# Project.net
KiCad netlist of a schematic drawn in Altium Designer
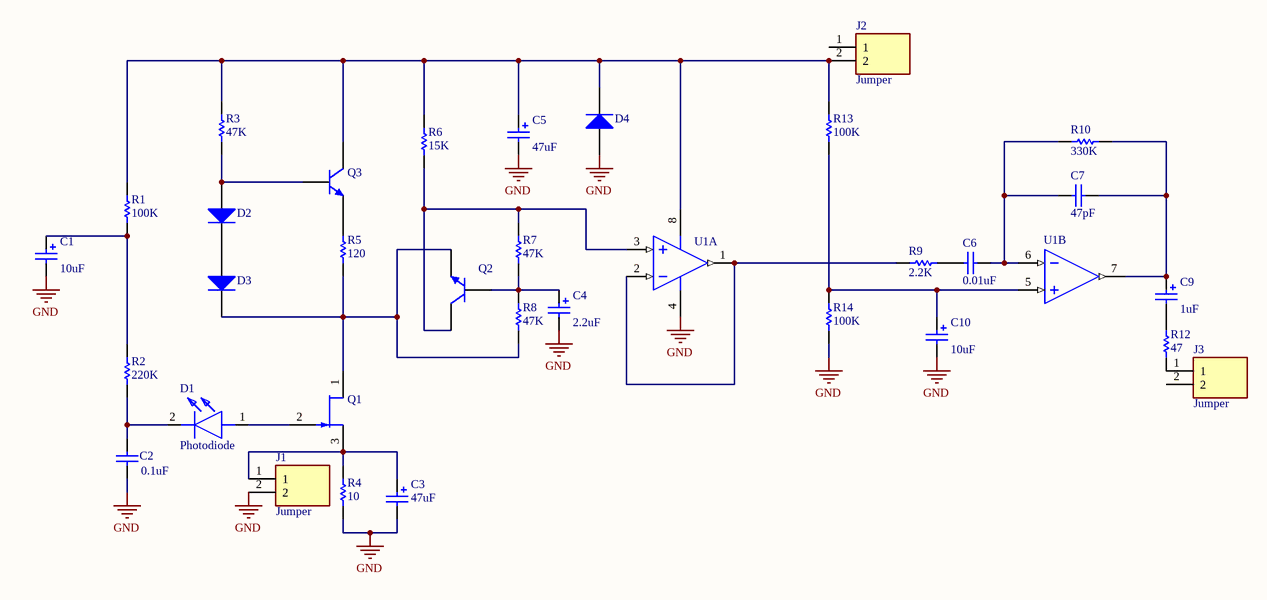
[diagram p0: Project.SchDoc]

(export (version "E")
  (design (tool "Eeschema 10.0.6"))
  (components
    (comp (ref "C1")
      (value "10uF")
      (footprint "Capacitor - Pol")
      (description "Polarized Capacitor (Radial)")
      (fields (field (name "Comment") "Cap Pol1") (field (name "PUBLISHER") "Altium Limited"))
      (libsource (lib "Standar_Components") (part "Cap Pol1"))
    )
    (comp (ref "C2")
      (value "0.1uF")
      (footprint "Capacitor")
      (description "Capacitor")
      (fields (field (name "Comment") "Cap") (field (name "PUBLISHER") "Altium Limited"))
      (libsource (lib "Standar_Components") (part "Cap"))
    )
    (comp (ref "C3")
      (value "47uF")
      (footprint "Capacitor - Pol")
      (description "Polarized Capacitor (Radial)")
      (fields (field (name "Comment") "Cap Pol1") (field (name "PUBLISHER") "Altium Limited"))
      (libsource (lib "Standar_Components") (part "Cap Pol1"))
    )
    (comp (ref "C4")
      (value "2.2uF")
      (footprint "Capacitor - Pol")
      (description "Polarized Capacitor (Radial)")
      (fields (field (name "Comment") "Cap Pol1") (field (name "PUBLISHER") "Altium Limited"))
      (libsource (lib "Standar_Components") (part "Cap Pol1"))
    )
    (comp (ref "C5")
      (value "47uF")
      (footprint "Capacitor - Pol")
      (description "Polarized Capacitor (Radial)")
      (fields (field (name "Comment") "Cap Pol1") (field (name "PUBLISHER") "Altium Limited"))
      (libsource (lib "Standar_Components") (part "Cap Pol1"))
    )
    (comp (ref "C6")
      (value "0.01uF")
      (footprint "Capacitor")
      (description "Capacitor")
      (fields (field (name "Comment") "Cap") (field (name "PUBLISHER") "Altium Limited"))
      (libsource (lib "Standar_Components") (part "Cap"))
    )
    (comp (ref "C7")
      (value "47pF")
      (footprint "Capacitor")
      (description "Capacitor")
      (fields (field (name "Comment") "Cap") (field (name "PUBLISHER") "Altium Limited"))
      (libsource (lib "Standar_Components") (part "Cap"))
    )
    (comp (ref "C9")
      (value "1uF")
      (footprint "Capacitor - Pol")
      (description "Polarized Capacitor (Radial)")
      (fields (field (name "Comment") "Cap Pol1") (field (name "PUBLISHER") "Altium Limited"))
      (libsource (lib "Standar_Components") (part "Cap Pol1"))
    )
    (comp (ref "C10")
      (value "10uF")
      (footprint "Capacitor - Pol")
      (description "Polarized Capacitor (Radial)")
      (fields (field (name "Comment") "Cap Pol1") (field (name "PUBLISHER") "Altium Limited"))
      (libsource (lib "Standar_Components") (part "Cap Pol1"))
    )
    (comp (ref "D1")
      (value "Photodiode")
      (footprint "Diode")
      (libsource (lib "Standar_Components") (part "Photodiode"))
    )
    (comp (ref "D2")
      (value "Diode 1N5408")
      (footprint "Diode")
      (description "3 Amp Medium Power Silicon Rectifier Diode")
      (fields (field (name "PUBLISHER") "Altium Limited"))
      (libsource (lib "Standar_Components") (part "Diode 1N5408"))
    )
    (comp (ref "D3")
      (value "Diode 1N5408")
      (footprint "Diode")
      (description "3 Amp Medium Power Silicon Rectifier Diode")
      (fields (field (name "PUBLISHER") "Altium Limited"))
      (libsource (lib "Standar_Components") (part "Diode 1N5408"))
    )
    (comp (ref "D4")
      (value "Diode 1N5408")
      (footprint "Diode")
      (description "3 Amp Medium Power Silicon Rectifier Diode")
      (fields (field (name "PUBLISHER") "Altium Limited"))
      (libsource (lib "Standar_Components") (part "Diode 1N5408"))
    )
    (comp (ref "J1")
      (value "Jumper")
      (footprint "JUMPER")
      (libsource (lib "Standar_Components") (part "Jumper"))
    )
    (comp (ref "J2")
      (value "Jumper")
      (footprint "JUMPER")
      (libsource (lib "Standar_Components") (part "Jumper"))
    )
    (comp (ref "J3")
      (value "Jumper")
      (footprint "JUMPER")
      (libsource (lib "Standar_Components") (part "Jumper"))
    )
    (comp (ref "Q1")
      (value "JFET-N")
      (footprint "TRANSISTOR")
      (description "N-Channel JFET")
      (fields (field (name "PUBLISHER") "Altium Limited"))
      (libsource (lib "Standar_Components") (part "JFET-N"))
    )
    (comp (ref "Q2")
      (value "NPN")
      (footprint "TRANSISTOR")
      (description "NPN Bipolar Transistor")
      (fields (field (name "PUBLISHER") "Altium Limited"))
      (libsource (lib "Standar_Components") (part "NPN"))
    )
    (comp (ref "Q3")
      (value "NPN")
      (footprint "TRANSISTOR")
      (description "NPN Bipolar Transistor")
      (fields (field (name "PUBLISHER") "Altium Limited"))
      (libsource (lib "Standar_Components") (part "NPN"))
    )
    (comp (ref "R1")
      (value "100K")
      (footprint "RES - Axial 0.6")
      (description "Resistor")
      (fields (field (name "Comment") "Res1") (field (name "PUBLISHER") "Altium Limited"))
      (libsource (lib "Standar_Components") (part "Res1"))
    )
    (comp (ref "R2")
      (value "220K")
      (footprint "RES - Axial 0.6")
      (description "Resistor")
      (fields (field (name "Comment") "Res1") (field (name "PUBLISHER") "Altium Limited"))
      (libsource (lib "Standar_Components") (part "Res1"))
    )
    (comp (ref "R3")
      (value "47K")
      (footprint "RES - Axial 0.6")
      (description "Resistor")
      (fields (field (name "Comment") "Res1") (field (name "PUBLISHER") "Altium Limited"))
      (libsource (lib "Standar_Components") (part "Res1"))
    )
    (comp (ref "R4")
      (value "10")
      (footprint "RES - Axial 0.6")
      (description "Resistor")
      (fields (field (name "Comment") "Res1") (field (name "PUBLISHER") "Altium Limited"))
      (libsource (lib "Standar_Components") (part "Res1"))
    )
    (comp (ref "R5")
      (value "120")
      (footprint "RES - Axial 0.6")
      (description "Resistor")
      (fields (field (name "Comment") "Res1") (field (name "PUBLISHER") "Altium Limited"))
      (libsource (lib "Standar_Components") (part "Res1"))
    )
    (comp (ref "R6")
      (value "15K")
      (footprint "RES - Axial 0.6")
      (description "Resistor")
      (fields (field (name "Comment") "Res1") (field (name "PUBLISHER") "Altium Limited"))
      (libsource (lib "Standar_Components") (part "Res1"))
    )
    (comp (ref "R7")
      (value "47K")
      (footprint "RES - Axial 0.6")
      (description "Resistor")
      (fields (field (name "Comment") "Res1") (field (name "PUBLISHER") "Altium Limited"))
      (libsource (lib "Standar_Components") (part "Res1"))
    )
    (comp (ref "R8")
      (value "47K")
      (footprint "RES - Axial 0.6")
      (description "Resistor")
      (fields (field (name "Comment") "Res1") (field (name "PUBLISHER") "Altium Limited"))
      (libsource (lib "Standar_Components") (part "Res1"))
    )
    (comp (ref "R9")
      (value "2.2K")
      (footprint "RES - Axial 0.6")
      (description "Resistor")
      (fields (field (name "Comment") "Res1") (field (name "PUBLISHER") "Altium Limited"))
      (libsource (lib "Standar_Components") (part "Res1"))
    )
    (comp (ref "R10")
      (value "330K")
      (footprint "RES - Axial 0.6")
      (description "Resistor")
      (fields (field (name "Comment") "Res1") (field (name "PUBLISHER") "Altium Limited"))
      (libsource (lib "Standar_Components") (part "Res1"))
    )
    (comp (ref "R12")
      (value "47")
      (footprint "RES - Axial 0.6")
      (description "Resistor")
      (fields (field (name "Comment") "Res1") (field (name "PUBLISHER") "Altium Limited"))
      (libsource (lib "Standar_Components") (part "Res1"))
    )
    (comp (ref "R13")
      (value "100K")
      (footprint "RES - Axial 0.6")
      (description "Resistor")
      (fields (field (name "Comment") "Res1") (field (name "PUBLISHER") "Altium Limited"))
      (libsource (lib "Standar_Components") (part "Res1"))
    )
    (comp (ref "R14")
      (value "100K")
      (footprint "RES - Axial 0.6")
      (description "Resistor")
      (fields (field (name "Comment") "Res1") (field (name "PUBLISHER") "Altium Limited"))
      (libsource (lib "Standar_Components") (part "Res1"))
    )
    (comp (ref "U1")
      (value "LM833N/NOPB")
      (footprint "DIP8")
      (description "AUDIO AMPLIFIER")
      (fields (field (name "MANUFACTURER") "TI National Semiconductor"))
      (libsource (lib "Components") (part "LM833N/NOPB"))
    )
  )
  (nets
    (net (code "1") (name "GND") (class "Default")
      (node (ref "C1") (pin "2") (pinfunction "2_2") (pintype "passive"))
      (node (ref "C10") (pin "2") (pinfunction "2_2") (pintype "passive"))
      (node (ref "C2") (pin "1") (pinfunction "1_1") (pintype "passive"))
      (node (ref "C3") (pin "2") (pinfunction "2_2") (pintype "passive"))
      (node (ref "C4") (pin "2") (pinfunction "2_2") (pintype "passive"))
      (node (ref "C5") (pin "2") (pinfunction "2_2") (pintype "passive"))
      (node (ref "D4") (pin "1") (pinfunction "A_1") (pintype "passive"))
      (node (ref "J1") (pin "2") (pinfunction "2_2") (pintype "passive"))
      (node (ref "R14") (pin "1") (pinfunction "1_1") (pintype "passive"))
      (node (ref "R4") (pin "1") (pinfunction "1_1") (pintype "passive"))
      (node (ref "U1") (pin "4") (pinfunction "V-_4") (pintype "power_in"))
    )
    (net (code "2") (name "Net-(C1-Pad1)") (class "Default")
      (node (ref "C1") (pin "1") (pinfunction "1_1") (pintype "passive"))
      (node (ref "R1") (pin "1") (pinfunction "1_1") (pintype "passive"))
      (node (ref "R2") (pin "2") (pinfunction "2_2") (pintype "passive"))
    )
    (net (code "3") (name "Net-(C6-Pad2)") (class "Default")
      (node (ref "C6") (pin "2") (pinfunction "2_2") (pintype "passive"))
      (node (ref "R9") (pin "1") (pinfunction "1_1") (pintype "passive"))
    )
    (net (code "4") (name "Net-(C9-Pad2)") (class "Default")
      (node (ref "C9") (pin "2") (pinfunction "2_2") (pintype "passive"))
      (node (ref "R12") (pin "2") (pinfunction "2_2") (pintype "passive"))
    )
    (net (code "5") (name "Net-(D1-A)") (class "Default")
      (node (ref "D1") (pin "1") (pinfunction "A_1") (pintype "passive"))
      (node (ref "Q1") (pin "2") (pinfunction "G_2") (pintype "passive"))
    )
    (net (code "6") (name "Net-(D1-K)") (class "Default")
      (node (ref "C2") (pin "2") (pinfunction "2_2") (pintype "passive"))
      (node (ref "D1") (pin "2") (pinfunction "K_2") (pintype "passive"))
      (node (ref "R2") (pin "1") (pinfunction "1_1") (pintype "passive"))
    )
    (net (code "7") (name "Net-(D2-A)") (class "Default")
      (node (ref "D2") (pin "1") (pinfunction "A_1") (pintype "passive"))
      (node (ref "Q3") (pin "2") (pinfunction "B_2") (pintype "passive"))
      (node (ref "R3") (pin "1") (pinfunction "1_1") (pintype "passive"))
    )
    (net (code "8") (name "Net-(D2-K)") (class "Default")
      (node (ref "D2") (pin "2") (pinfunction "K_2") (pintype "passive"))
      (node (ref "D3") (pin "1") (pinfunction "A_1") (pintype "passive"))
    )
    (net (code "9") (name "Net-(D3-K)") (class "Default")
      (node (ref "D3") (pin "2") (pinfunction "K_2") (pintype "passive"))
      (node (ref "Q1") (pin "1") (pinfunction "D_1") (pintype "passive"))
      (node (ref "Q2") (pin "3") (pinfunction "E_3") (pintype "passive"))
      (node (ref "R5") (pin "1") (pinfunction "1_1") (pintype "passive"))
      (node (ref "R8") (pin "1") (pinfunction "1_1") (pintype "passive"))
    )
    (net (code "10") (name "Net-(D4-K)") (class "Default")
      (node (ref "C5") (pin "1") (pinfunction "1_1") (pintype "passive"))
      (node (ref "D4") (pin "2") (pinfunction "K_2") (pintype "passive"))
      (node (ref "J2") (pin "2") (pinfunction "2_2") (pintype "passive"))
      (node (ref "Q3") (pin "1") (pinfunction "C_1") (pintype "passive"))
      (node (ref "R1") (pin "2") (pinfunction "2_2") (pintype "passive"))
      (node (ref "R13") (pin "2") (pinfunction "2_2") (pintype "passive"))
      (node (ref "R3") (pin "2") (pinfunction "2_2") (pintype "passive"))
      (node (ref "R6") (pin "2") (pinfunction "2_2") (pintype "passive"))
      (node (ref "U1") (pin "8") (pinfunction "TAB_8") (pintype "power_in"))
    )
    (net (code "11") (name "Net-(J3-Pad1)") (class "Default")
      (node (ref "J3") (pin "1") (pinfunction "1_1") (pintype "passive"))
      (node (ref "R12") (pin "1") (pinfunction "1_1") (pintype "passive"))
    )
    (net (code "12") (name "Net-(Q1-S)") (class "Default")
      (node (ref "C3") (pin "1") (pinfunction "1_1") (pintype "passive"))
      (node (ref "J1") (pin "1") (pinfunction "1_1") (pintype "passive"))
      (node (ref "Q1") (pin "3") (pinfunction "S_3") (pintype "passive"))
      (node (ref "R4") (pin "2") (pinfunction "2_2") (pintype "passive"))
    )
    (net (code "13") (name "Net-(Q2-B)") (class "Default")
      (node (ref "C4") (pin "1") (pinfunction "1_1") (pintype "passive"))
      (node (ref "Q2") (pin "2") (pinfunction "B_2") (pintype "passive"))
      (node (ref "R7") (pin "1") (pinfunction "1_1") (pintype "passive"))
      (node (ref "R8") (pin "2") (pinfunction "2_2") (pintype "passive"))
    )
    (net (code "14") (name "Net-(Q2-C)") (class "Default")
      (node (ref "Q2") (pin "1") (pinfunction "C_1") (pintype "passive"))
      (node (ref "R6") (pin "1") (pinfunction "1_1") (pintype "passive"))
      (node (ref "R7") (pin "2") (pinfunction "2_2") (pintype "passive"))
      (node (ref "U1") (pin "3") (pinfunction "IN+_3") (pintype "input"))
    )
    (net (code "15") (name "Net-(Q3-E)") (class "Default")
      (node (ref "Q3") (pin "3") (pinfunction "E_3") (pintype "passive"))
      (node (ref "R5") (pin "2") (pinfunction "2_2") (pintype "passive"))
    )
    (net (code "16") (name "Net-(U1A-IN-)") (class "Default")
      (node (ref "R9") (pin "2") (pinfunction "2_2") (pintype "passive"))
      (node (ref "U1") (pin "1") (pinfunction "OS_NUL_1") (pintype "output"))
      (node (ref "U1") (pin "2") (pinfunction "IN-_2") (pintype "input"))
    )
    (net (code "17") (name "Net-(U1B-OS_NUL)") (class "Default")
      (node (ref "C10") (pin "1") (pinfunction "1_1") (pintype "passive"))
      (node (ref "R13") (pin "1") (pinfunction "1_1") (pintype "passive"))
      (node (ref "R14") (pin "2") (pinfunction "2_2") (pintype "passive"))
      (node (ref "U1") (pin "5") (pinfunction "OS_NUL_5") (pintype "input"))
    )
    (net (code "18") (name "Net-(U1B-OUT)") (class "Default")
      (node (ref "C6") (pin "1") (pinfunction "1_1") (pintype "passive"))
      (node (ref "C7") (pin "2") (pinfunction "2_2") (pintype "passive"))
      (node (ref "R10") (pin "2") (pinfunction "2_2") (pintype "passive"))
      (node (ref "U1") (pin "6") (pinfunction "OUT_6") (pintype "input"))
    )
    (net (code "19") (name "Net-(U1B-V+)") (class "Default")
      (node (ref "C7") (pin "1") (pinfunction "1_1") (pintype "passive"))
      (node (ref "C9") (pin "1") (pinfunction "1_1") (pintype "passive"))
      (node (ref "R10") (pin "1") (pinfunction "1_1") (pintype "passive"))
      (node (ref "U1") (pin "7") (pinfunction "V+_7") (pintype "output"))
    )
    (net (code "20") (name "unconnected-(J2-Pad1)") (class "Default")
      (node (ref "J2") (pin "1") (pinfunction "1_1") (pintype "passive"))
    )
    (net (code "21") (name "unconnected-(J3-Pad2)") (class "Default")
      (node (ref "J3") (pin "2") (pinfunction "2_2") (pintype "passive"))
    )
  )
)
